# Adafruit_Ultimate_GPS_USB.net
KiCad netlist of a schematic drawn in EAGLE
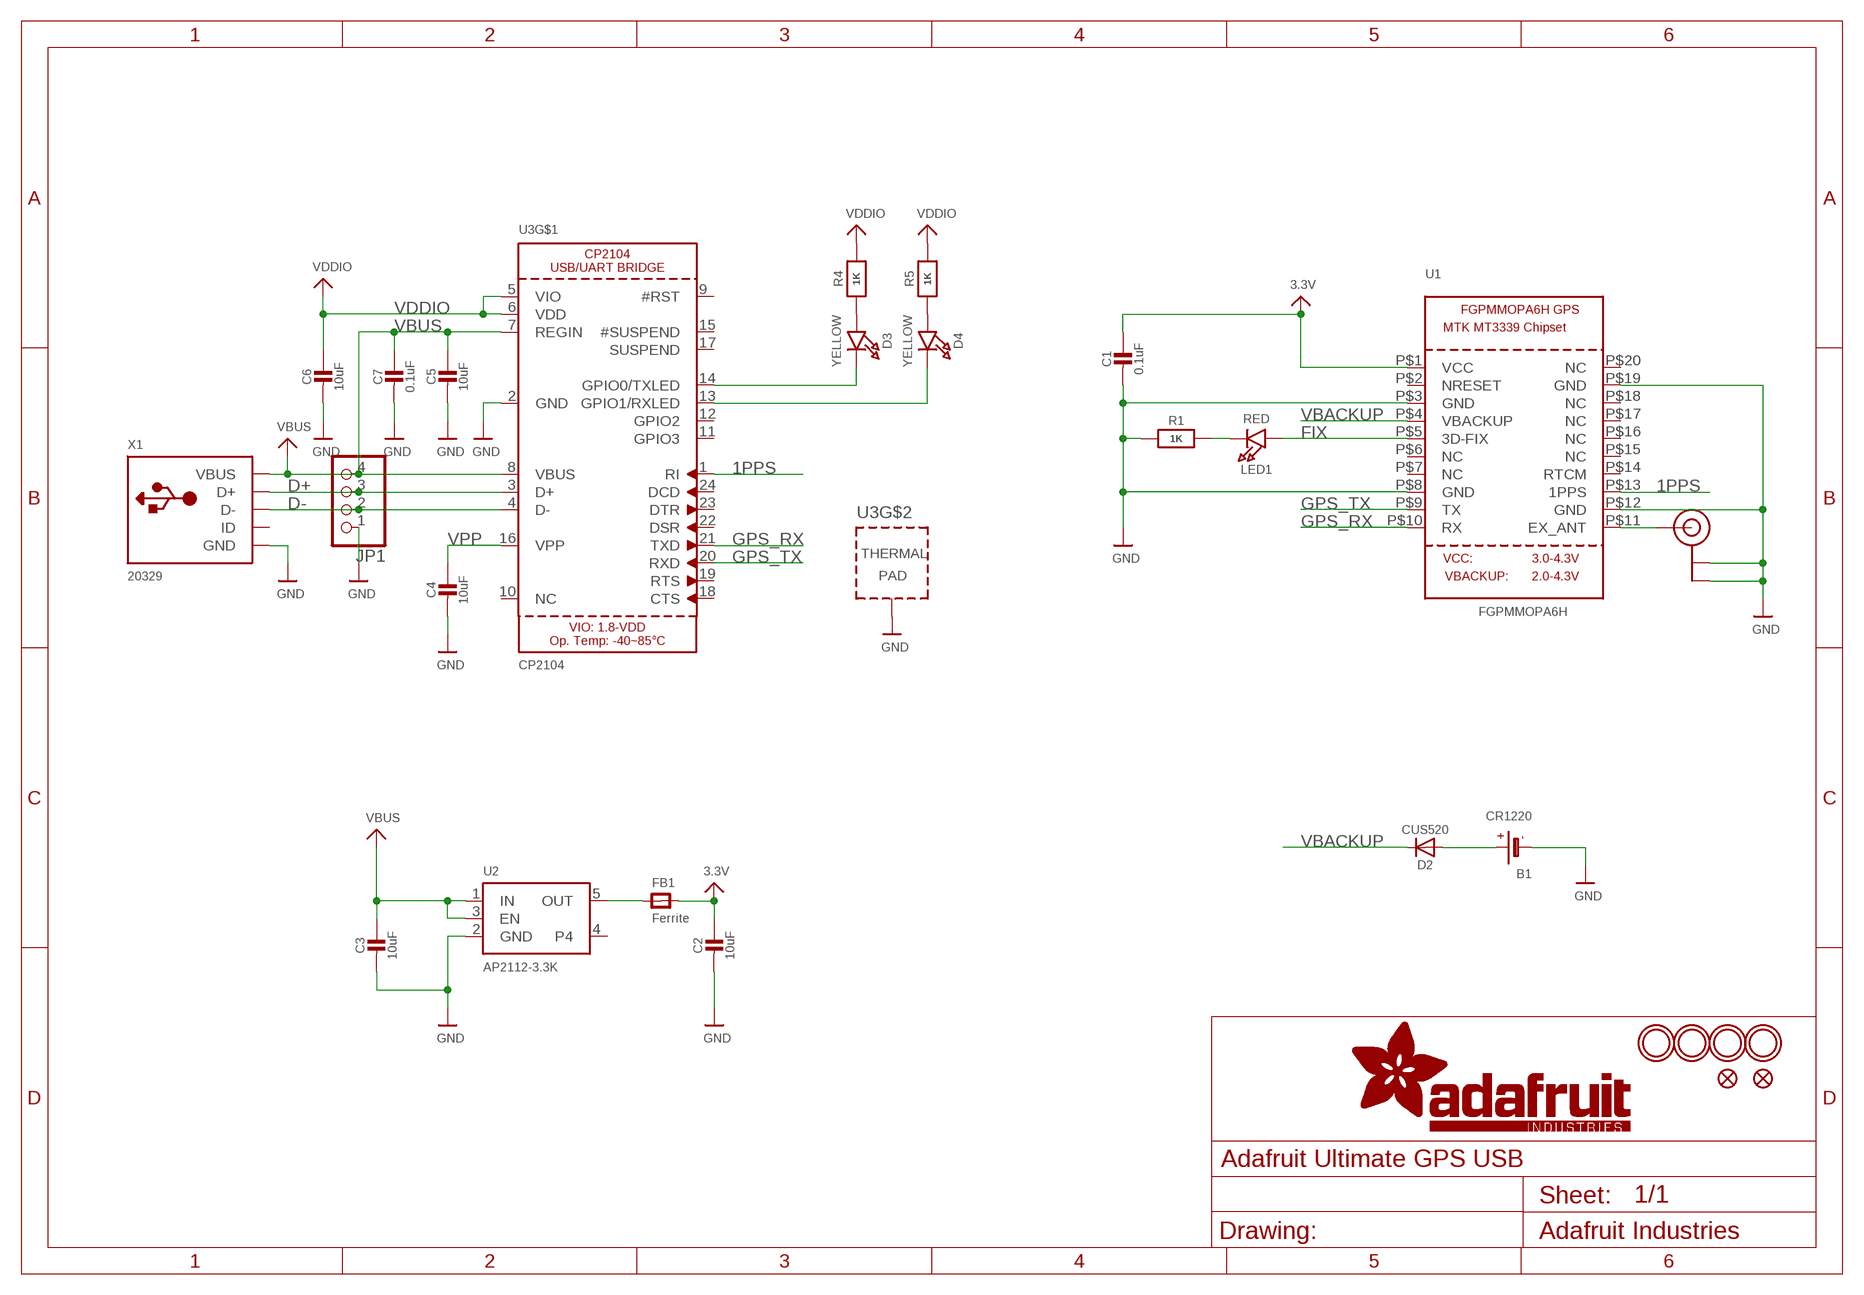
[diagram p0: schematic, sheet 1]

(export (version "E")
  (design (tool "Eeschema 10.0.6"))
  (components
    (comp (ref "B1")
      (value "CR1220")
      (footprint "eagle-import:CR1220")
      (libsource (lib "eagle-import") (part "BATTERYCR1220_SMT"))
    )
    (comp (ref "C1")
      (value "0.1uF")
      (footprint "eagle-import:0603-NO")
      (libsource (lib "eagle-import") (part "CAP_CERAMIC0603_NO"))
    )
    (comp (ref "C2")
      (value "10uF")
      (footprint "eagle-import:0805-NO")
      (libsource (lib "eagle-import") (part "CAP_CERAMIC0805-NOOUTLINE"))
    )
    (comp (ref "C3")
      (value "10uF")
      (footprint "eagle-import:0805-NO")
      (libsource (lib "eagle-import") (part "CAP_CERAMIC0805-NOOUTLINE"))
    )
    (comp (ref "C4")
      (value "10uF")
      (footprint "eagle-import:0805-NO")
      (libsource (lib "eagle-import") (part "CAP_CERAMIC0805-NOOUTLINE"))
    )
    (comp (ref "C5")
      (value "10uF")
      (footprint "eagle-import:0805-NO")
      (libsource (lib "eagle-import") (part "CAP_CERAMIC0805-NOOUTLINE"))
    )
    (comp (ref "C6")
      (value "10uF")
      (footprint "eagle-import:0805-NO")
      (libsource (lib "eagle-import") (part "CAP_CERAMIC0805-NOOUTLINE"))
    )
    (comp (ref "C7")
      (value "0.1uF")
      (footprint "eagle-import:0603-NO")
      (libsource (lib "eagle-import") (part "CAP_CERAMIC0603_NO"))
    )
    (comp (ref "D2")
      (value "CUS520")
      (footprint "eagle-import:SOD-323")
      (libsource (lib "eagle-import") (part "DIODESOD-323"))
    )
    (comp (ref "D3")
      (value "YELLOW")
      (footprint "eagle-import:CHIPLED_0805_NOOUTLINE")
      (libsource (lib "eagle-import") (part "LED0805_NOOUTLINE"))
    )
    (comp (ref "D4")
      (value "YELLOW")
      (footprint "eagle-import:CHIPLED_0805_NOOUTLINE")
      (libsource (lib "eagle-import") (part "LED0805_NOOUTLINE"))
    )
    (comp (ref "FB1")
      (value "Ferrite")
      (footprint "eagle-import:0805-NO")
      (libsource (lib "eagle-import") (part "FERRITE-0805NO"))
    )
    (comp (ref "FID1")
      (value "FIDUCIAL_1MM")
      (footprint "eagle-import:FIDUCIAL_1MM")
      (libsource (lib "eagle-import") (part "FIDUCIAL_1MM"))
    )
    (comp (ref "FID2")
      (value "FIDUCIAL_1MM")
      (footprint "eagle-import:FIDUCIAL_1MM")
      (libsource (lib "eagle-import") (part "FIDUCIAL_1MM"))
    )
    (comp (ref "JP1")
      (value "HEADER-1X4ROUND")
      (footprint "eagle-import:1X04_ROUND")
      (libsource (lib "eagle-import") (part "HEADER-1X4ROUND"))
    )
    (comp (ref "LED1")
      (value "RED")
      (footprint "eagle-import:CHIPLED_0805_NOOUTLINE")
      (libsource (lib "eagle-import") (part "LED0805_NOOUTLINE"))
    )
    (comp (ref "R1")
      (value "1K")
      (footprint "eagle-import:0603-NO")
      (libsource (lib "eagle-import") (part "RESISTOR_0603_NOOUT"))
    )
    (comp (ref "R4")
      (value "1K")
      (footprint "eagle-import:0603-NO")
      (libsource (lib "eagle-import") (part "RESISTOR_0603_NOOUT"))
    )
    (comp (ref "R5")
      (value "1K")
      (footprint "eagle-import:0603-NO")
      (libsource (lib "eagle-import") (part "RESISTOR_0603_NOOUT"))
    )
    (comp (ref "U$8")
      (value "MOUNTINGHOLE2.5")
      (footprint "eagle-import:MOUNTINGHOLE_2.5_PLATED")
      (libsource (lib "eagle-import") (part "MOUNTINGHOLE2.5"))
    )
    (comp (ref "U$9")
      (value "MOUNTINGHOLE2.5")
      (footprint "eagle-import:MOUNTINGHOLE_2.5_PLATED")
      (libsource (lib "eagle-import") (part "MOUNTINGHOLE2.5"))
    )
    (comp (ref "U$20")
      (value "U.FL")
      (footprint "eagle-import:U.FL")
      (libsource (lib "eagle-import") (part "U.FL"))
    )
    (comp (ref "U$35")
      (value "MOUNTINGHOLE2.5")
      (footprint "eagle-import:MOUNTINGHOLE_2.5_PLATED")
      (libsource (lib "eagle-import") (part "MOUNTINGHOLE2.5"))
    )
    (comp (ref "U$36")
      (value "MOUNTINGHOLE2.5")
      (footprint "eagle-import:MOUNTINGHOLE_2.5_PLATED")
      (libsource (lib "eagle-import") (part "MOUNTINGHOLE2.5"))
    )
    (comp (ref "U1")
      (value "FGPMMOPA6H")
      (footprint "eagle-import:FGPMMOPA6H")
      (libsource (lib "eagle-import") (part "GPS_FGPMMOPA6H"))
    )
    (comp (ref "U2")
      (value "AP2112-3.3K")
      (footprint "eagle-import:SOT23-5")
      (libsource (lib "eagle-import") (part "VREG_SOT23-5"))
    )
    (comp (ref "U3")
      (value "CP2104")
      (footprint "eagle-import:QFN24_4MM_SMSC")
      (libsource (lib "eagle-import") (part "CP2104"))
    )
    (comp (ref "X1")
      (value "20329")
      (footprint "eagle-import:4UCONN_20329_V2")
      (libsource (lib "eagle-import") (part "USB_MICRO_20329_V2"))
    )
  )
  (nets
    (net (code "1") (name "/1PPS") (class "Default")
      (node (ref "U1") (pin "P$13") (pinfunction "1PPS_P$13") (pintype "bidirectional"))
      (node (ref "U3") (pin "1") (pinfunction "RI_1") (pintype "input"))
    )
    (net (code "2") (name "/D+") (class "Default")
      (node (ref "JP1") (pin "3") (pinfunction "3_3") (pintype "passive"))
      (node (ref "U3") (pin "3") (pinfunction "D+_3") (pintype "bidirectional"))
      (node (ref "X1") (pin "D+") (pinfunction "D+_D+") (pintype "bidirectional"))
    )
    (net (code "3") (name "/D-") (class "Default")
      (node (ref "JP1") (pin "2") (pinfunction "2_2") (pintype "passive"))
      (node (ref "U3") (pin "4") (pinfunction "D-_4") (pintype "bidirectional"))
      (node (ref "X1") (pin "D-") (pinfunction "D-_D-") (pintype "bidirectional"))
    )
    (net (code "4") (name "/FIX") (class "Default")
      (node (ref "LED1") (pin "A") (pinfunction "A_A") (pintype "passive"))
      (node (ref "U1") (pin "P$5") (pinfunction "3D-FIX_P$5") (pintype "bidirectional"))
    )
    (net (code "5") (name "/GPS_RX") (class "Default")
      (node (ref "U1") (pin "P$10") (pinfunction "RX_P$10") (pintype "bidirectional"))
      (node (ref "U3") (pin "21") (pinfunction "TXD_21") (pintype "output"))
    )
    (net (code "6") (name "/GPS_TX") (class "Default")
      (node (ref "U1") (pin "P$9") (pinfunction "TX_P$9") (pintype "bidirectional"))
      (node (ref "U3") (pin "20") (pinfunction "RXD_20") (pintype "input"))
    )
    (net (code "7") (name "/VBACKUP") (class "Default")
      (node (ref "D2") (pin "C") (pinfunction "C_C") (pintype "passive"))
      (node (ref "U1") (pin "P$4") (pinfunction "VBACKUP_P$4") (pintype "bidirectional"))
    )
    (net (code "8") (name "/VPP") (class "Default")
      (node (ref "C4") (pin "1") (pinfunction "1_1") (pintype "passive"))
      (node (ref "U3") (pin "16") (pinfunction "VPP_16") (pintype "bidirectional"))
    )
    (net (code "9") (name "3.3V") (class "Default")
      (node (ref "C1") (pin "1") (pinfunction "1_1") (pintype "passive"))
      (node (ref "C2") (pin "1") (pinfunction "1_1") (pintype "passive"))
      (node (ref "FB1") (pin "2") (pinfunction "P$2_2") (pintype "passive"))
      (node (ref "U1") (pin "P$1") (pinfunction "VCC_P$1") (pintype "bidirectional"))
    )
    (net (code "10") (name "GND") (class "Default")
      (node (ref "B1") (pin "-") (pinfunction "-_-") (pintype "passive"))
      (node (ref "C1") (pin "2") (pinfunction "2_2") (pintype "passive"))
      (node (ref "C2") (pin "2") (pinfunction "2_2") (pintype "passive"))
      (node (ref "C3") (pin "2") (pinfunction "2_2") (pintype "passive"))
      (node (ref "C4") (pin "2") (pinfunction "2_2") (pintype "passive"))
      (node (ref "C5") (pin "2") (pinfunction "2_2") (pintype "passive"))
      (node (ref "C6") (pin "2") (pinfunction "2_2") (pintype "passive"))
      (node (ref "C7") (pin "2") (pinfunction "2_2") (pintype "passive"))
      (node (ref "JP1") (pin "1") (pinfunction "1_1") (pintype "passive"))
      (node (ref "R1") (pin "1") (pinfunction "1_1") (pintype "passive"))
      (node (ref "U$20") (pin "P$1") (pinfunction "GND_P$1") (pintype "bidirectional"))
      (node (ref "U$20") (pin "P$2") (pinfunction "GND_P$2") (pintype "bidirectional"))
      (node (ref "U1") (pin "P$12") (pinfunction "GND_P$12") (pintype "bidirectional"))
      (node (ref "U1") (pin "P$19") (pinfunction "GND_P$19") (pintype "bidirectional"))
      (node (ref "U1") (pin "P$3") (pinfunction "GND_P$3") (pintype "bidirectional"))
      (node (ref "U1") (pin "P$8") (pinfunction "GND_P$8") (pintype "bidirectional"))
      (node (ref "U2") (pin "2") (pinfunction "GND_2") (pintype "power_in"))
      (node (ref "U3") (pin "2") (pinfunction "GND_2") (pintype "power_in"))
      (node (ref "U3") (pin "THERM") (pinfunction "TP_THERM") (pintype "power_in"))
      (node (ref "X1") (pin "BASE@1") (pinfunction "GND_BASE@1") (pintype "power_in"))
      (node (ref "X1") (pin "BASE@2") (pinfunction "GND_BASE@2") (pintype "power_in"))
      (node (ref "X1") (pin "GND") (pinfunction "GND_GND") (pintype "power_in"))
      (node (ref "X1") (pin "SPRT@1") (pinfunction "GND_SPRT@1") (pintype "power_in"))
      (node (ref "X1") (pin "SPRT@2") (pinfunction "GND_SPRT@2") (pintype "power_in"))
      (node (ref "X1") (pin "SPRT@3") (pinfunction "GND_SPRT@3") (pintype "power_in"))
      (node (ref "X1") (pin "SPRT@4") (pinfunction "GND_SPRT@4") (pintype "power_in"))
    )
    (net (code "11") (name "Net-(B1-+-Pad+$1)") (class "Default")
      (node (ref "B1") (pin "+$1") (pinfunction "+_+$1") (pintype "passive"))
      (node (ref "B1") (pin "+$2") (pinfunction "+_+$2") (pintype "passive"))
      (node (ref "D2") (pin "A") (pinfunction "A_A") (pintype "passive"))
    )
    (net (code "12") (name "Net-(D3-PadA)") (class "Default")
      (node (ref "D3") (pin "A") (pinfunction "A_A") (pintype "passive"))
      (node (ref "R4") (pin "1") (pinfunction "1_1") (pintype "passive"))
    )
    (net (code "13") (name "Net-(D4-PadA)") (class "Default")
      (node (ref "D4") (pin "A") (pinfunction "A_A") (pintype "passive"))
      (node (ref "R5") (pin "1") (pinfunction "1_1") (pintype "passive"))
    )
    (net (code "14") (name "Net-(FB1-P$1)") (class "Default")
      (node (ref "FB1") (pin "1") (pinfunction "P$1_1") (pintype "passive"))
      (node (ref "U2") (pin "5") (pinfunction "OUT_5") (pintype "power_in"))
    )
    (net (code "15") (name "Net-(LED1-PadC)") (class "Default")
      (node (ref "LED1") (pin "C") (pinfunction "C_C") (pintype "passive"))
      (node (ref "R1") (pin "2") (pinfunction "2_2") (pintype "passive"))
    )
    (net (code "16") (name "Net-(U$20-SIGNAL)") (class "Default")
      (node (ref "U$20") (pin "P$3") (pinfunction "SIGNAL_P$3") (pintype "bidirectional"))
      (node (ref "U1") (pin "P$11") (pinfunction "EX_ANT_P$11") (pintype "bidirectional"))
    )
    (net (code "17") (name "Net-(U3A-GPIO0{slash}TXLED)") (class "Default")
      (node (ref "D3") (pin "C") (pinfunction "C_C") (pintype "passive"))
      (node (ref "U3") (pin "14") (pinfunction "GPIO0/TXLED_14") (pintype "bidirectional"))
    )
    (net (code "18") (name "Net-(U3A-GPIO1{slash}RXLED)") (class "Default")
      (node (ref "D4") (pin "C") (pinfunction "C_C") (pintype "passive"))
      (node (ref "U3") (pin "13") (pinfunction "GPIO1/RXLED_13") (pintype "bidirectional"))
    )
    (net (code "19") (name "VBUS") (class "Default")
      (node (ref "C3") (pin "1") (pinfunction "1_1") (pintype "passive"))
      (node (ref "C5") (pin "1") (pinfunction "1_1") (pintype "passive"))
      (node (ref "C7") (pin "1") (pinfunction "1_1") (pintype "passive"))
      (node (ref "JP1") (pin "4") (pinfunction "4_4") (pintype "passive"))
      (node (ref "U2") (pin "1") (pinfunction "IN_1") (pintype "power_in"))
      (node (ref "U2") (pin "3") (pinfunction "EN_3") (pintype "input"))
      (node (ref "U3") (pin "7") (pinfunction "REGIN_7") (pintype "power_in"))
      (node (ref "U3") (pin "8") (pinfunction "VBUS_8") (pintype "power_in"))
      (node (ref "X1") (pin "VBUS") (pinfunction "VBUS_VBUS") (pintype "power_in"))
    )
    (net (code "20") (name "VDDIO") (class "Default")
      (node (ref "C6") (pin "1") (pinfunction "1_1") (pintype "passive"))
      (node (ref "R4") (pin "2") (pinfunction "2_2") (pintype "passive"))
      (node (ref "R5") (pin "2") (pinfunction "2_2") (pintype "passive"))
      (node (ref "U3") (pin "5") (pinfunction "VIO_5") (pintype "power_in"))
      (node (ref "U3") (pin "6") (pinfunction "VDD_6") (pintype "power_in"))
    )
    (net (code "21") (name "unconnected-(U1-NC-PadP$6)") (class "Default")
      (node (ref "U1") (pin "P$6") (pinfunction "NC_P$6") (pintype "bidirectional"))
    )
    (net (code "22") (name "unconnected-(U1-NC-PadP$7)") (class "Default")
      (node (ref "U1") (pin "P$7") (pinfunction "NC_P$7") (pintype "bidirectional"))
    )
    (net (code "23") (name "unconnected-(U1-NC-PadP$15)") (class "Default")
      (node (ref "U1") (pin "P$15") (pinfunction "NC_P$15") (pintype "bidirectional"))
    )
    (net (code "24") (name "unconnected-(U1-NC-PadP$16)") (class "Default")
      (node (ref "U1") (pin "P$16") (pinfunction "NC_P$16") (pintype "bidirectional"))
    )
    (net (code "25") (name "unconnected-(U1-NC-PadP$17)") (class "Default")
      (node (ref "U1") (pin "P$17") (pinfunction "NC_P$17") (pintype "bidirectional"))
    )
    (net (code "26") (name "unconnected-(U1-NC-PadP$18)") (class "Default")
      (node (ref "U1") (pin "P$18") (pinfunction "NC_P$18") (pintype "bidirectional"))
    )
    (net (code "27") (name "unconnected-(U1-NC-PadP$20)") (class "Default")
      (node (ref "U1") (pin "P$20") (pinfunction "NC_P$20") (pintype "bidirectional"))
    )
    (net (code "28") (name "unconnected-(U1-NRESET-PadP$2)") (class "Default")
      (node (ref "U1") (pin "P$2") (pinfunction "NRESET_P$2") (pintype "bidirectional"))
    )
    (net (code "29") (name "unconnected-(U1-RTCM-PadP$14)") (class "Default")
      (node (ref "U1") (pin "P$14") (pinfunction "RTCM_P$14") (pintype "bidirectional"))
    )
    (net (code "30") (name "unconnected-(U2-P4-Pad4)") (class "Default")
      (node (ref "U2") (pin "4") (pinfunction "P4_4") (pintype "bidirectional"))
    )
    (net (code "31") (name "unconnected-(U3A-#RST-Pad9)") (class "Default")
      (node (ref "U3") (pin "9") (pinfunction "#RST_9") (pintype "bidirectional"))
    )
    (net (code "32") (name "unconnected-(U3A-#SUSPEND-Pad15)") (class "Default")
      (node (ref "U3") (pin "15") (pinfunction "#SUSPEND_15") (pintype "output"))
    )
    (net (code "33") (name "unconnected-(U3A-CTS-Pad18)") (class "Default")
      (node (ref "U3") (pin "18") (pinfunction "CTS_18") (pintype "input"))
    )
    (net (code "34") (name "unconnected-(U3A-DCD-Pad24)") (class "Default")
      (node (ref "U3") (pin "24") (pinfunction "DCD_24") (pintype "input"))
    )
    (net (code "35") (name "unconnected-(U3A-DSR-Pad22)") (class "Default")
      (node (ref "U3") (pin "22") (pinfunction "DSR_22") (pintype "input"))
    )
    (net (code "36") (name "unconnected-(U3A-DTR-Pad23)") (class "Default")
      (node (ref "U3") (pin "23") (pinfunction "DTR_23") (pintype "output"))
    )
    (net (code "37") (name "unconnected-(U3A-GPIO2-Pad12)") (class "Default")
      (node (ref "U3") (pin "12") (pinfunction "GPIO2_12") (pintype "bidirectional"))
    )
    (net (code "38") (name "unconnected-(U3A-GPIO3-Pad11)") (class "Default")
      (node (ref "U3") (pin "11") (pinfunction "GPIO3_11") (pintype "bidirectional"))
    )
    (net (code "39") (name "unconnected-(U3A-NC-Pad10)") (class "Default")
      (node (ref "U3") (pin "10") (pinfunction "NC_10") (pintype "no_connect"))
    )
    (net (code "40") (name "unconnected-(U3A-RTS-Pad19)") (class "Default")
      (node (ref "U3") (pin "19") (pinfunction "RTS_19") (pintype "output"))
    )
    (net (code "41") (name "unconnected-(U3A-SUSPEND-Pad17)") (class "Default")
      (node (ref "U3") (pin "17") (pinfunction "SUSPEND_17") (pintype "output"))
    )
    (net (code "42") (name "unconnected-(X1-PadID)") (class "Default")
      (node (ref "X1") (pin "ID") (pinfunction "ID_ID") (pintype "bidirectional"))
    )
  )
)
